# Buzzer.net
KiCad netlist of a schematic drawn in Altium Designer
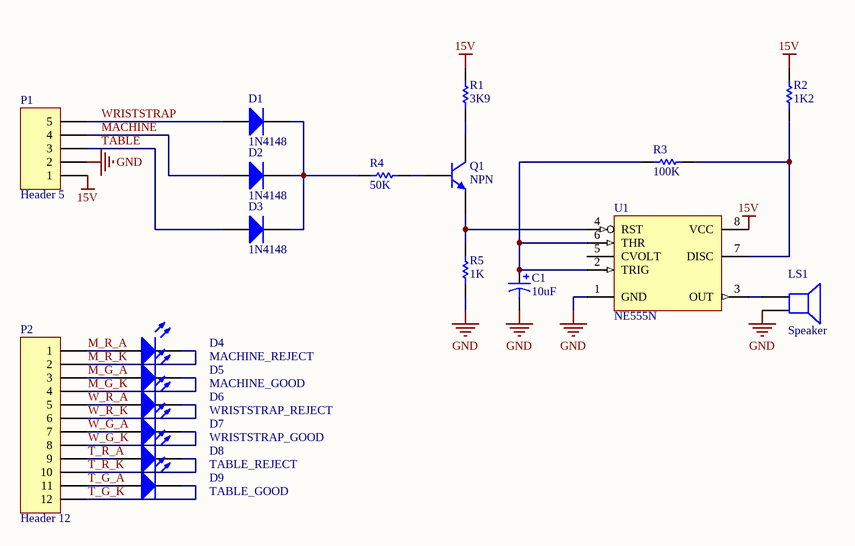
[diagram p0: Buzzer.SchDoc]

(export (version "E")
  (design (tool "Eeschema 10.0.6"))
  (components
    (comp (ref "C1")
      (value "10uF")
      (footprint "toko-Embedded:E2,5-5")
      (description "Polarized Capacitor (Radial)")
      (fields (field (name "PUBLISHER") "Altium Limited"))
      (libsource (lib "Miscellaneous Devices") (part "Cap Pol1"))
    )
    (comp (ref "D1")
      (value "1N4148")
      (footprint "toko-Embedded:DO34Z7")
      (description "Default Diode")
      (fields (field (name "PUBLISHER") "Altium Limited"))
      (libsource (lib "Miscellaneous Devices") (part "Diode"))
    )
    (comp (ref "D2")
      (value "1N4148")
      (footprint "toko-Embedded:DO34Z7")
      (description "Default Diode")
      (fields (field (name "PUBLISHER") "Altium Limited"))
      (libsource (lib "Miscellaneous Devices") (part "Diode"))
    )
    (comp (ref "D3")
      (value "1N4148")
      (footprint "toko-Embedded:DO34Z7")
      (description "Default Diode")
      (fields (field (name "PUBLISHER") "Altium Limited"))
      (libsource (lib "Miscellaneous Devices") (part "Diode"))
    )
    (comp (ref "D4")
      (value "MACHINE_REJECT")
      (footprint "toko-Embedded:LED5MM")
      (description "Typical INFRARED GaAs LED")
      (fields (field (name "PUBLISHER") "Altium Limited"))
      (libsource (lib "Miscellaneous Devices") (part "LED0"))
    )
    (comp (ref "D5")
      (value "MACHINE_GOOD")
      (footprint "toko-Embedded:LED5MM")
      (description "Typical INFRARED GaAs LED")
      (fields (field (name "PUBLISHER") "Altium Limited"))
      (libsource (lib "Miscellaneous Devices") (part "LED0"))
    )
    (comp (ref "D6")
      (value "WRISTSTRAP_REJECT")
      (footprint "toko-Embedded:LED5MM")
      (description "Typical INFRARED GaAs LED")
      (fields (field (name "PUBLISHER") "Altium Limited"))
      (libsource (lib "Miscellaneous Devices") (part "LED0"))
    )
    (comp (ref "D7")
      (value "WRISTSTRAP_GOOD")
      (footprint "toko-Embedded:LED5MM")
      (description "Typical INFRARED GaAs LED")
      (fields (field (name "PUBLISHER") "Altium Limited"))
      (libsource (lib "Miscellaneous Devices") (part "LED0"))
    )
    (comp (ref "D8")
      (value "TABLE_REJECT")
      (footprint "toko-Embedded:LED5MM")
      (description "Typical INFRARED GaAs LED")
      (fields (field (name "PUBLISHER") "Altium Limited"))
      (libsource (lib "Miscellaneous Devices") (part "LED0"))
    )
    (comp (ref "D9")
      (value "TABLE_GOOD")
      (footprint "toko-Embedded:LED5MM")
      (description "Typical INFRARED GaAs LED")
      (fields (field (name "PUBLISHER") "Altium Limited"))
      (libsource (lib "Miscellaneous Devices") (part "LED0"))
    )
    (comp (ref "LS1")
      (value "Speaker")
      (footprint "toko-Embedded:BUZZER-16MM")
      (description "Loudspeaker")
      (fields (field (name "PUBLISHER") "Altium Limited"))
      (libsource (lib "Miscellaneous Devices") (part "Speaker"))
    )
    (comp (ref "P1")
      (value "Header 5")
      (footprint "toko-Embedded:7395-05")
      (description "Header, 5-Pin")
      (fields (field (name "PUBLISHER") "Altium Limited"))
      (libsource (lib "Miscellaneous Connectors") (part "Header 5"))
    )
    (comp (ref "P2")
      (value "Header 12")
      (footprint "toko-Embedded:7395-12")
      (description "Header, 12-Pin")
      (fields (field (name "PUBLISHER") "Altium Limited"))
      (libsource (lib "Miscellaneous Connectors") (part "Header 12"))
    )
    (comp (ref "Q1")
      (value "NPN")
      (footprint "toko-Embedded:TO92")
      (description "NPN Bipolar Transistor")
      (fields (field (name "PUBLISHER") "Altium Limited"))
      (libsource (lib "Miscellaneous Devices") (part "NPN"))
    )
    (comp (ref "R1")
      (value "3K9")
      (footprint "toko-Embedded:0207/10")
      (description "Resistor")
      (fields (field (name "PUBLISHER") "Altium Limited"))
      (libsource (lib "Miscellaneous Devices") (part "Res1"))
    )
    (comp (ref "R2")
      (value "1K2")
      (footprint "toko-Embedded:0207/10")
      (description "Resistor")
      (fields (field (name "PUBLISHER") "Altium Limited"))
      (libsource (lib "Miscellaneous Devices") (part "Res1"))
    )
    (comp (ref "R3")
      (value "100K")
      (footprint "toko-Embedded:0207/10")
      (description "Resistor")
      (fields (field (name "PUBLISHER") "Altium Limited"))
      (libsource (lib "Miscellaneous Devices") (part "Res1"))
    )
    (comp (ref "R4")
      (value "50K")
      (footprint "toko-Embedded:0207/10")
      (description "Resistor")
      (fields (field (name "PUBLISHER") "Altium Limited"))
      (libsource (lib "Miscellaneous Devices") (part "Res1"))
    )
    (comp (ref "R5")
      (value "1K")
      (footprint "toko-Embedded:0207/10")
      (description "Resistor")
      (fields (field (name "PUBLISHER") "Altium Limited"))
      (libsource (lib "Miscellaneous Devices") (part "Res1"))
    )
    (comp (ref "U1")
      (value "NE555N")
      (footprint "DIP8")
      (description "General-Purpose Single Bipolar Timer")
      (fields (field (name "PUBLISHER") "Altium Limited"))
      (libsource (lib "ST Analog Timer Circuit") (part "NE555N"))
    )
  )
  (nets
    (net (code "1") (name "/MACHINE") (class "Default")
      (node (ref "D2") (pin "1") (pinfunction "A_1") (pintype "passive"))
      (node (ref "P1") (pin "4") (pinfunction "4_4") (pintype "passive"))
    )
    (net (code "2") (name "/M_G_A") (class "Default")
      (node (ref "D5") (pin "1") (pinfunction "A_1") (pintype "passive"))
      (node (ref "P2") (pin "3") (pinfunction "3_3") (pintype "passive"))
    )
    (net (code "3") (name "/M_G_K") (class "Default")
      (node (ref "D5") (pin "2") (pinfunction "K_2") (pintype "passive"))
      (node (ref "P2") (pin "4") (pinfunction "4_4") (pintype "passive"))
    )
    (net (code "4") (name "/M_R_A") (class "Default")
      (node (ref "D4") (pin "1") (pinfunction "A_1") (pintype "passive"))
      (node (ref "P2") (pin "1") (pinfunction "1_1") (pintype "passive"))
    )
    (net (code "5") (name "/M_R_K") (class "Default")
      (node (ref "D4") (pin "2") (pinfunction "K_2") (pintype "passive"))
      (node (ref "P2") (pin "2") (pinfunction "2_2") (pintype "passive"))
    )
    (net (code "6") (name "/TABLE") (class "Default")
      (node (ref "D3") (pin "1") (pinfunction "A_1") (pintype "passive"))
      (node (ref "P1") (pin "3") (pinfunction "3_3") (pintype "passive"))
    )
    (net (code "7") (name "/T_G_A") (class "Default")
      (node (ref "D9") (pin "1") (pinfunction "A_1") (pintype "passive"))
      (node (ref "P2") (pin "11") (pinfunction "11_11") (pintype "passive"))
    )
    (net (code "8") (name "/T_G_K") (class "Default")
      (node (ref "D9") (pin "2") (pinfunction "K_2") (pintype "passive"))
      (node (ref "P2") (pin "12") (pinfunction "12_12") (pintype "passive"))
    )
    (net (code "9") (name "/T_R_A") (class "Default")
      (node (ref "D8") (pin "1") (pinfunction "A_1") (pintype "passive"))
      (node (ref "P2") (pin "9") (pinfunction "9_9") (pintype "passive"))
    )
    (net (code "10") (name "/T_R_K") (class "Default")
      (node (ref "D8") (pin "2") (pinfunction "K_2") (pintype "passive"))
      (node (ref "P2") (pin "10") (pinfunction "10_10") (pintype "passive"))
    )
    (net (code "11") (name "/WRISTSTRAP") (class "Default")
      (node (ref "D1") (pin "1") (pinfunction "A_1") (pintype "passive"))
      (node (ref "P1") (pin "5") (pinfunction "5_5") (pintype "passive"))
    )
    (net (code "12") (name "/W_G_A") (class "Default")
      (node (ref "D7") (pin "1") (pinfunction "A_1") (pintype "passive"))
      (node (ref "P2") (pin "7") (pinfunction "7_7") (pintype "passive"))
    )
    (net (code "13") (name "/W_G_K") (class "Default")
      (node (ref "D7") (pin "2") (pinfunction "K_2") (pintype "passive"))
      (node (ref "P2") (pin "8") (pinfunction "8_8") (pintype "passive"))
    )
    (net (code "14") (name "/W_R_A") (class "Default")
      (node (ref "D6") (pin "1") (pinfunction "A_1") (pintype "passive"))
      (node (ref "P2") (pin "5") (pinfunction "5_5") (pintype "passive"))
    )
    (net (code "15") (name "/W_R_K") (class "Default")
      (node (ref "D6") (pin "2") (pinfunction "K_2") (pintype "passive"))
      (node (ref "P2") (pin "6") (pinfunction "6_6") (pintype "passive"))
    )
    (net (code "16") (name "15V") (class "Default")
      (node (ref "P1") (pin "1") (pinfunction "1_1") (pintype "passive"))
      (node (ref "R1") (pin "2") (pinfunction "2_2") (pintype "passive"))
      (node (ref "R2") (pin "2") (pinfunction "2_2") (pintype "passive"))
      (node (ref "U1") (pin "8") (pinfunction "VCC_8") (pintype "power_in"))
    )
    (net (code "17") (name "GND") (class "Default")
      (node (ref "C1") (pin "2") (pinfunction "2_2") (pintype "passive"))
      (node (ref "LS1") (pin "2") (pinfunction "2_2") (pintype "passive"))
      (node (ref "P1") (pin "2") (pinfunction "2_2") (pintype "passive"))
      (node (ref "R5") (pin "1") (pinfunction "1_1") (pintype "passive"))
      (node (ref "U1") (pin "1") (pinfunction "GND_1") (pintype "power_in"))
    )
    (net (code "18") (name "Net-(D1-K)") (class "Default")
      (node (ref "D1") (pin "2") (pinfunction "K_2") (pintype "passive"))
      (node (ref "D2") (pin "2") (pinfunction "K_2") (pintype "passive"))
      (node (ref "D3") (pin "2") (pinfunction "K_2") (pintype "passive"))
      (node (ref "R4") (pin "1") (pinfunction "1_1") (pintype "passive"))
    )
    (net (code "19") (name "Net-(Q1-B)") (class "Default")
      (node (ref "Q1") (pin "2") (pinfunction "B_2") (pintype "passive"))
      (node (ref "R4") (pin "2") (pinfunction "2_2") (pintype "passive"))
    )
    (net (code "20") (name "Net-(Q1-C)") (class "Default")
      (node (ref "Q1") (pin "1") (pinfunction "C_1") (pintype "passive"))
      (node (ref "R1") (pin "1") (pinfunction "1_1") (pintype "passive"))
    )
    (net (code "21") (name "Net-(Q1-E)") (class "Default")
      (node (ref "Q1") (pin "3") (pinfunction "E_3") (pintype "passive"))
      (node (ref "R5") (pin "2") (pinfunction "2_2") (pintype "passive"))
      (node (ref "U1") (pin "4") (pinfunction "RST_4") (pintype "input"))
    )
    (net (code "22") (name "Net-(U1-DISC)") (class "Default")
      (node (ref "R2") (pin "1") (pinfunction "1_1") (pintype "passive"))
      (node (ref "R3") (pin "2") (pinfunction "2_2") (pintype "passive"))
      (node (ref "U1") (pin "7") (pinfunction "DISC_7") (pintype "open_collector"))
    )
    (net (code "23") (name "Net-(U1-OUT)") (class "Default")
      (node (ref "LS1") (pin "1") (pinfunction "1_1") (pintype "passive"))
      (node (ref "U1") (pin "3") (pinfunction "OUT_3") (pintype "output"))
    )
    (net (code "24") (name "Net-(U1-THR)") (class "Default")
      (node (ref "C1") (pin "1") (pinfunction "1_1") (pintype "passive"))
      (node (ref "R3") (pin "1") (pinfunction "1_1") (pintype "passive"))
      (node (ref "U1") (pin "2") (pinfunction "TRIG_2") (pintype "input"))
      (node (ref "U1") (pin "6") (pinfunction "THR_6") (pintype "input"))
    )
    (net (code "25") (name "unconnected-(U1-CVOLT-Pad5)") (class "Default")
      (node (ref "U1") (pin "5") (pinfunction "CVOLT_5") (pintype "passive"))
    )
  )
)
